# Gen7Extension.net
KiCad netlist of a schematic drawn in EAGLE
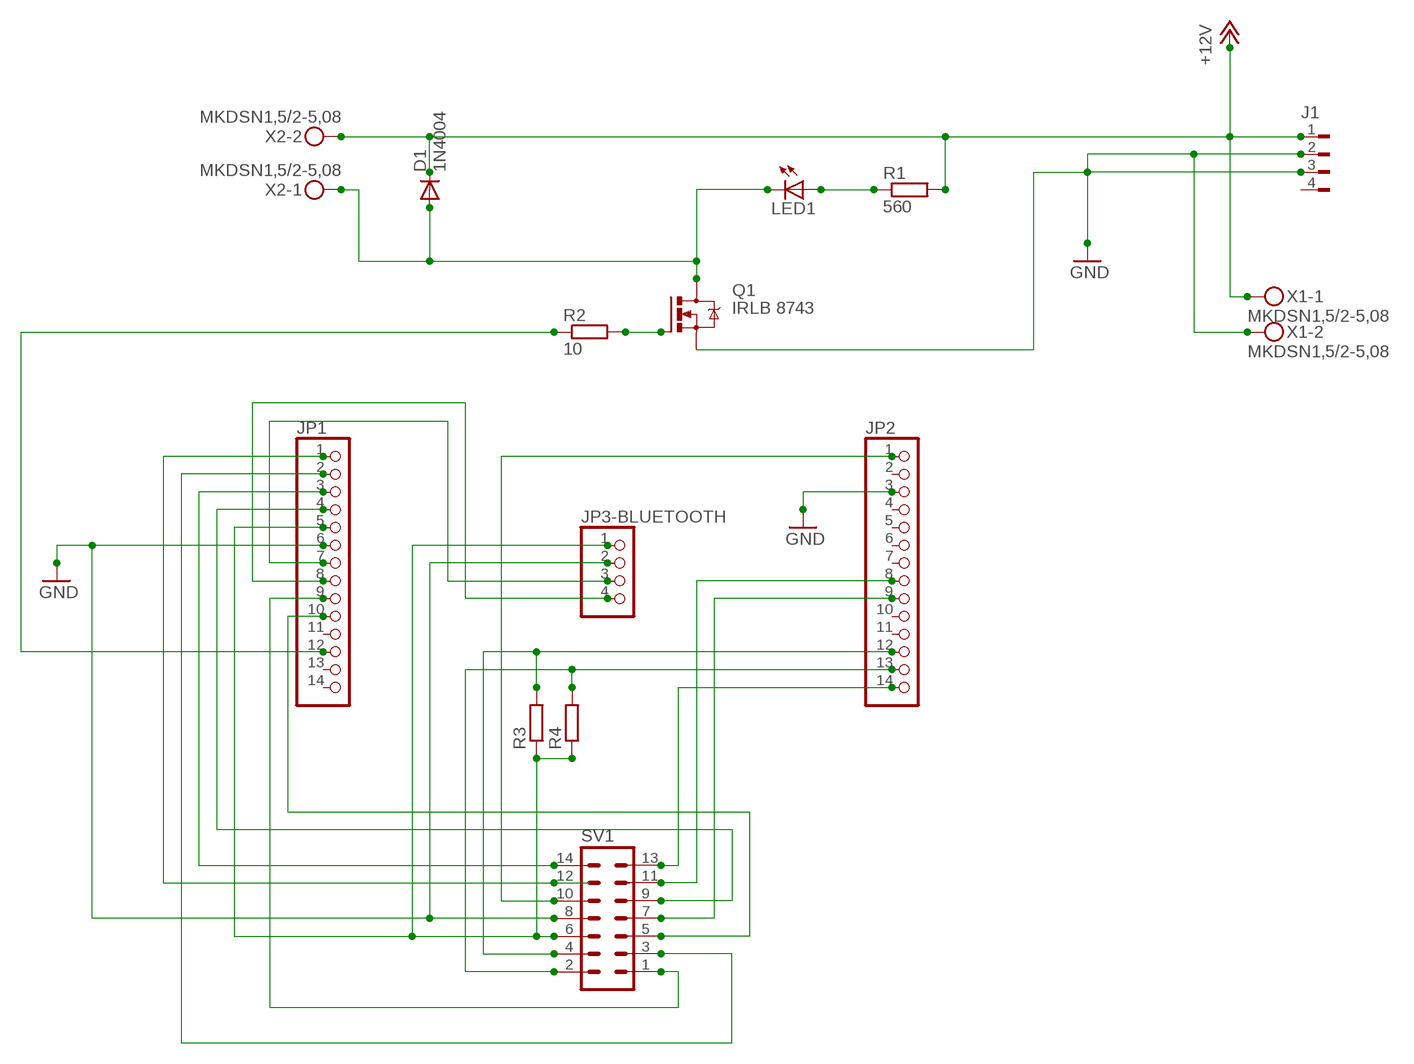
[diagram p0: schematic, sheet 1]

(export (version "E")
  (design (tool "Eeschema 10.0.6"))
  (components
    (comp (ref "D1")
      (value "1N4004")
      (footprint "eagle-import:DO41-10")
      (libsource (lib "eagle-import") (part "1N4004"))
    )
    (comp (ref "J1")
      (value "FLOPPY-4")
      (footprint "eagle-import:FLOPPY-4")
      (libsource (lib "eagle-import") (part "FLOPPY-4"))
    )
    (comp (ref "JP1")
      (value "PINHD-1X14")
      (footprint "eagle-import:1X14")
      (libsource (lib "eagle-import") (part "PINHD-1X14"))
    )
    (comp (ref "JP2")
      (value "PINHD-1X14")
      (footprint "eagle-import:1X14")
      (libsource (lib "eagle-import") (part "PINHD-1X14"))
    )
    (comp (ref "JP3-BLUETOOTH")
      (value "PINHD-1X4")
      (footprint "eagle-import:1X04")
      (libsource (lib "eagle-import") (part "PINHD-1X4"))
    )
    (comp (ref "LED1")
      (value "LED3MM")
      (footprint "eagle-import:LED3MM")
      (libsource (lib "eagle-import") (part "LED3MM"))
    )
    (comp (ref "Q1")
      (value "IRLB 8743")
      (footprint "eagle-import:TO220BV")
      (libsource (lib "eagle-import") (part "IRF530"))
    )
    (comp (ref "R1")
      (value "560")
      (footprint "eagle-import:0207_10")
      (libsource (lib "eagle-import") (part "R-EU_0207/10"))
    )
    (comp (ref "R2")
      (value "10")
      (footprint "eagle-import:0207_10")
      (libsource (lib "eagle-import") (part "R-EU_0207/10"))
    )
    (comp (ref "R3")
      (value "R-EU_0207/5V")
      (footprint "eagle-import:0207_5V")
      (libsource (lib "eagle-import") (part "R-EU_0207/5V"))
    )
    (comp (ref "R4")
      (value "R-EU_0207/2V")
      (footprint "eagle-import:0207_2V")
      (libsource (lib "eagle-import") (part "R-EU_0207/2V"))
    )
    (comp (ref "SV1")
      (value "ML14")
      (footprint "eagle-import:ML14")
      (libsource (lib "eagle-import") (part "ML14"))
    )
    (comp (ref "X1")
      (value "MKDSN1,5/2-5,08")
      (footprint "eagle-import:MKDSN1,5_2-5,08")
      (fields (field (name "MPN") "MKDSN 1,5/2-5.08"))
      (libsource (lib "eagle-import") (part "MKDSN1,5/2-5,08"))
    )
    (comp (ref "X2")
      (value "MKDSN1,5/2-5,08")
      (footprint "eagle-import:MKDSN1,5_2-5,08")
      (fields (field (name "MPN") "MKDSN 1,5/2-5.08"))
      (libsource (lib "eagle-import") (part "MKDSN1,5/2-5,08"))
    )
  )
  (nets
    (net (code "1") (name "+12V") (class "Default")
      (node (ref "D1") (pin "C") (pinfunction "C_C") (pintype "passive"))
      (node (ref "J1") (pin "1") (pinfunction "1_1") (pintype "passive"))
      (node (ref "R1") (pin "2") (pinfunction "2_2") (pintype "passive"))
      (node (ref "X1") (pin "1") (pinfunction "KL_1") (pintype "passive"))
      (node (ref "X2") (pin "2") (pinfunction "KL_2") (pintype "passive"))
    )
    (net (code "2") (name "GND") (class "Default")
      (node (ref "J1") (pin "2") (pinfunction "2_2") (pintype "passive"))
      (node (ref "J1") (pin "3") (pinfunction "3_3") (pintype "passive"))
      (node (ref "JP1") (pin "6") (pinfunction "6_6") (pintype "passive"))
      (node (ref "JP2") (pin "3") (pinfunction "3_3") (pintype "passive"))
      (node (ref "JP3-BLUETOOTH") (pin "2") (pinfunction "2_2") (pintype "passive"))
      (node (ref "Q1") (pin "S") (pinfunction "S_S") (pintype "passive"))
      (node (ref "SV1") (pin "8") (pinfunction "8_8") (pintype "passive"))
      (node (ref "X1") (pin "2") (pinfunction "KL_2") (pintype "passive"))
    )
    (net (code "3") (name "Net-(JP1-Pad1)") (class "Default")
      (node (ref "JP1") (pin "1") (pinfunction "1_1") (pintype "passive"))
      (node (ref "SV1") (pin "12") (pinfunction "12_12") (pintype "passive"))
    )
    (net (code "4") (name "Net-(JP1-Pad2)") (class "Default")
      (node (ref "JP1") (pin "2") (pinfunction "2_2") (pintype "passive"))
      (node (ref "SV1") (pin "3") (pinfunction "3_3") (pintype "passive"))
    )
    (net (code "5") (name "Net-(JP1-Pad3)") (class "Default")
      (node (ref "JP1") (pin "3") (pinfunction "3_3") (pintype "passive"))
      (node (ref "SV1") (pin "14") (pinfunction "14_14") (pintype "passive"))
    )
    (net (code "6") (name "Net-(JP1-Pad4)") (class "Default")
      (node (ref "JP1") (pin "4") (pinfunction "4_4") (pintype "passive"))
      (node (ref "SV1") (pin "9") (pinfunction "9_9") (pintype "passive"))
    )
    (net (code "7") (name "Net-(JP1-Pad5)") (class "Default")
      (node (ref "JP1") (pin "5") (pinfunction "5_5") (pintype "passive"))
      (node (ref "JP3-BLUETOOTH") (pin "1") (pinfunction "1_1") (pintype "passive"))
      (node (ref "R3") (pin "1") (pinfunction "1_1") (pintype "passive"))
      (node (ref "R4") (pin "1") (pinfunction "1_1") (pintype "passive"))
      (node (ref "SV1") (pin "6") (pinfunction "6_6") (pintype "passive"))
    )
    (net (code "8") (name "Net-(JP1-Pad7)") (class "Default")
      (node (ref "JP1") (pin "7") (pinfunction "7_7") (pintype "passive"))
      (node (ref "JP3-BLUETOOTH") (pin "3") (pinfunction "3_3") (pintype "passive"))
    )
    (net (code "9") (name "Net-(JP1-Pad8)") (class "Default")
      (node (ref "JP1") (pin "8") (pinfunction "8_8") (pintype "passive"))
      (node (ref "JP3-BLUETOOTH") (pin "4") (pinfunction "4_4") (pintype "passive"))
    )
    (net (code "10") (name "Net-(JP1-Pad9)") (class "Default")
      (node (ref "JP1") (pin "9") (pinfunction "9_9") (pintype "passive"))
      (node (ref "SV1") (pin "1") (pinfunction "1_1") (pintype "passive"))
    )
    (net (code "11") (name "Net-(JP1-Pad10)") (class "Default")
      (node (ref "JP1") (pin "10") (pinfunction "10_10") (pintype "passive"))
      (node (ref "SV1") (pin "5") (pinfunction "5_5") (pintype "passive"))
    )
    (net (code "12") (name "Net-(JP1-Pad12)") (class "Default")
      (node (ref "JP1") (pin "12") (pinfunction "12_12") (pintype "passive"))
      (node (ref "R2") (pin "1") (pinfunction "1_1") (pintype "passive"))
    )
    (net (code "13") (name "Net-(JP2-Pad1)") (class "Default")
      (node (ref "JP2") (pin "1") (pinfunction "1_1") (pintype "passive"))
      (node (ref "SV1") (pin "10") (pinfunction "10_10") (pintype "passive"))
    )
    (net (code "14") (name "Net-(JP2-Pad8)") (class "Default")
      (node (ref "JP2") (pin "8") (pinfunction "8_8") (pintype "passive"))
      (node (ref "SV1") (pin "11") (pinfunction "11_11") (pintype "passive"))
    )
    (net (code "15") (name "Net-(JP2-Pad9)") (class "Default")
      (node (ref "JP2") (pin "9") (pinfunction "9_9") (pintype "passive"))
      (node (ref "SV1") (pin "7") (pinfunction "7_7") (pintype "passive"))
    )
    (net (code "16") (name "Net-(JP2-Pad12)") (class "Default")
      (node (ref "JP2") (pin "12") (pinfunction "12_12") (pintype "passive"))
      (node (ref "R3") (pin "2") (pinfunction "2_2") (pintype "passive"))
      (node (ref "SV1") (pin "4") (pinfunction "4_4") (pintype "passive"))
    )
    (net (code "17") (name "Net-(JP2-Pad13)") (class "Default")
      (node (ref "JP2") (pin "13") (pinfunction "13_13") (pintype "passive"))
      (node (ref "R4") (pin "2") (pinfunction "2_2") (pintype "passive"))
      (node (ref "SV1") (pin "2") (pinfunction "2_2") (pintype "passive"))
    )
    (net (code "18") (name "Net-(JP2-Pad14)") (class "Default")
      (node (ref "JP2") (pin "14") (pinfunction "14_14") (pintype "passive"))
      (node (ref "SV1") (pin "13") (pinfunction "13_13") (pintype "passive"))
    )
    (net (code "19") (name "Net-(LED1-C)") (class "Default")
      (node (ref "D1") (pin "A") (pinfunction "A_A") (pintype "passive"))
      (node (ref "LED1") (pin "K") (pinfunction "C_K") (pintype "passive"))
      (node (ref "Q1") (pin "D") (pinfunction "D_D") (pintype "passive"))
      (node (ref "X2") (pin "1") (pinfunction "KL_1") (pintype "passive"))
    )
    (net (code "20") (name "Net-(LED1-PadA)") (class "Default")
      (node (ref "LED1") (pin "A") (pinfunction "A_A") (pintype "passive"))
      (node (ref "R1") (pin "1") (pinfunction "1_1") (pintype "passive"))
    )
    (net (code "21") (name "Net-(Q1-PadG)") (class "Default")
      (node (ref "Q1") (pin "G") (pinfunction "G_G") (pintype "passive"))
      (node (ref "R2") (pin "2") (pinfunction "2_2") (pintype "passive"))
    )
    (net (code "22") (name "unconnected-(J1-Pad4)") (class "Default")
      (node (ref "J1") (pin "4") (pinfunction "4_4") (pintype "passive"))
    )
    (net (code "23") (name "unconnected-(JP1-Pad11)") (class "Default")
      (node (ref "JP1") (pin "11") (pinfunction "11_11") (pintype "passive"))
    )
    (net (code "24") (name "unconnected-(JP1-Pad13)") (class "Default")
      (node (ref "JP1") (pin "13") (pinfunction "13_13") (pintype "passive"))
    )
    (net (code "25") (name "unconnected-(JP1-Pad14)") (class "Default")
      (node (ref "JP1") (pin "14") (pinfunction "14_14") (pintype "passive"))
    )
    (net (code "26") (name "unconnected-(JP2-Pad2)") (class "Default")
      (node (ref "JP2") (pin "2") (pinfunction "2_2") (pintype "passive"))
    )
    (net (code "27") (name "unconnected-(JP2-Pad4)") (class "Default")
      (node (ref "JP2") (pin "4") (pinfunction "4_4") (pintype "passive"))
    )
    (net (code "28") (name "unconnected-(JP2-Pad5)") (class "Default")
      (node (ref "JP2") (pin "5") (pinfunction "5_5") (pintype "passive"))
    )
    (net (code "29") (name "unconnected-(JP2-Pad6)") (class "Default")
      (node (ref "JP2") (pin "6") (pinfunction "6_6") (pintype "passive"))
    )
    (net (code "30") (name "unconnected-(JP2-Pad7)") (class "Default")
      (node (ref "JP2") (pin "7") (pinfunction "7_7") (pintype "passive"))
    )
    (net (code "31") (name "unconnected-(JP2-Pad10)") (class "Default")
      (node (ref "JP2") (pin "10") (pinfunction "10_10") (pintype "passive"))
    )
    (net (code "32") (name "unconnected-(JP2-Pad11)") (class "Default")
      (node (ref "JP2") (pin "11") (pinfunction "11_11") (pintype "passive"))
    )
  )
)
